# ArduinoInterface_v2_1.net
KiCad netlist of a schematic drawn in EAGLE
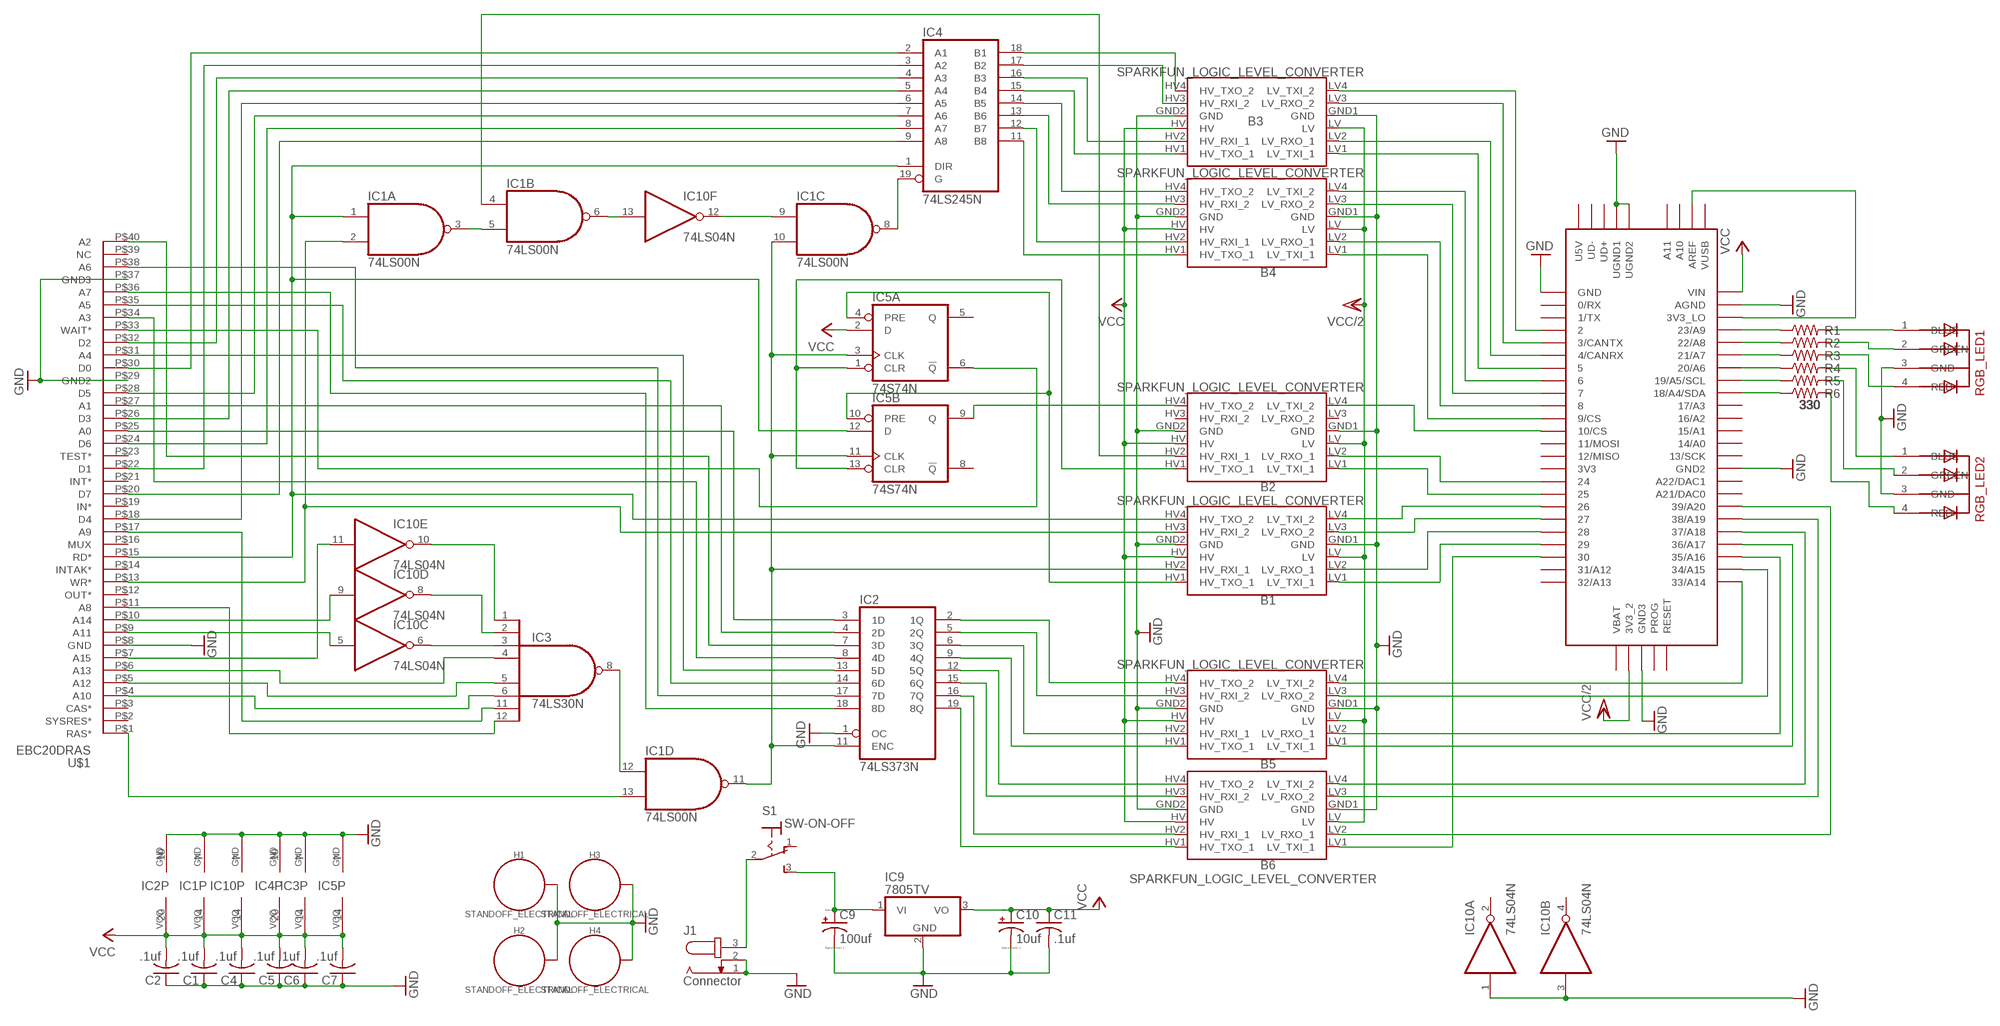
[diagram p0: schematic, sheet 1]

(export (version "E")
  (design (tool "Eeschema 10.0.6"))
  (components
    (comp (ref "B1")
      (value "SPARKFUN_LOGIC_LEVEL_CONVERTER")
      (footprint "eagle-import:SPARKFUN_LOGIC_LEVEL_CONVERTER")
      (libsource (lib "eagle-import") (part "SPARKFUN_LOGIC_LEVEL_CONVERTER"))
    )
    (comp (ref "B2")
      (value "SPARKFUN_LOGIC_LEVEL_CONVERTER")
      (footprint "eagle-import:SPARKFUN_LOGIC_LEVEL_CONVERTER")
      (libsource (lib "eagle-import") (part "SPARKFUN_LOGIC_LEVEL_CONVERTER"))
    )
    (comp (ref "B3")
      (value "SPARKFUN_LOGIC_LEVEL_CONVERTER")
      (footprint "eagle-import:SPARKFUN_LOGIC_LEVEL_CONVERTER")
      (libsource (lib "eagle-import") (part "SPARKFUN_LOGIC_LEVEL_CONVERTER"))
    )
    (comp (ref "B4")
      (value "SPARKFUN_LOGIC_LEVEL_CONVERTER")
      (footprint "eagle-import:SPARKFUN_LOGIC_LEVEL_CONVERTER")
      (libsource (lib "eagle-import") (part "SPARKFUN_LOGIC_LEVEL_CONVERTER"))
    )
    (comp (ref "B5")
      (value "SPARKFUN_LOGIC_LEVEL_CONVERTER")
      (footprint "eagle-import:SPARKFUN_LOGIC_LEVEL_CONVERTER")
      (libsource (lib "eagle-import") (part "SPARKFUN_LOGIC_LEVEL_CONVERTER"))
    )
    (comp (ref "B6")
      (value "SPARKFUN_LOGIC_LEVEL_CONVERTER")
      (footprint "eagle-import:SPARKFUN_LOGIC_LEVEL_CONVERTER")
      (libsource (lib "eagle-import") (part "SPARKFUN_LOGIC_LEVEL_CONVERTER"))
    )
    (comp (ref "C1")
      (value ".1uf")
      (footprint "eagle-import:C025-025X050")
      (libsource (lib "eagle-import") (part "C-US025-025X050"))
    )
    (comp (ref "C2")
      (value ".1uf")
      (footprint "eagle-import:C025-025X050")
      (libsource (lib "eagle-import") (part "C-US025-025X050"))
    )
    (comp (ref "C4")
      (value ".1uf")
      (footprint "eagle-import:C025-025X050")
      (libsource (lib "eagle-import") (part "C-US025-025X050"))
    )
    (comp (ref "C5")
      (value ".1uf")
      (footprint "eagle-import:C025-025X050")
      (libsource (lib "eagle-import") (part "C-US025-025X050"))
    )
    (comp (ref "C6")
      (value ".1uf")
      (footprint "eagle-import:C025-025X050")
      (libsource (lib "eagle-import") (part "C-US025-025X050"))
    )
    (comp (ref "C7")
      (value ".1uf")
      (footprint "eagle-import:C025-025X050")
      (libsource (lib "eagle-import") (part "C-US025-025X050"))
    )
    (comp (ref "C9")
      (value "100uf")
      (footprint "eagle-import:E5-6")
      (libsource (lib "eagle-import") (part "CPOL-USE5-6"))
    )
    (comp (ref "C10")
      (value "10uf")
      (footprint "eagle-import:E5-6")
      (libsource (lib "eagle-import") (part "CPOL-USE5-6"))
    )
    (comp (ref "C11")
      (value ".1uf")
      (footprint "eagle-import:C025-025X050")
      (libsource (lib "eagle-import") (part "C-US025-025X050"))
    )
    (comp (ref "H1")
      (value "STANDOFF_ELECTRICAL")
      (footprint "eagle-import:STANDOFF-ELECTRICAL")
      (libsource (lib "eagle-import") (part "STANDOFF_ELECTRICAL"))
    )
    (comp (ref "H2")
      (value "STANDOFF_ELECTRICAL")
      (footprint "eagle-import:STANDOFF-ELECTRICAL")
      (libsource (lib "eagle-import") (part "STANDOFF_ELECTRICAL"))
    )
    (comp (ref "H3")
      (value "STANDOFF_ELECTRICAL")
      (footprint "eagle-import:STANDOFF-ELECTRICAL")
      (libsource (lib "eagle-import") (part "STANDOFF_ELECTRICAL"))
    )
    (comp (ref "H4")
      (value "STANDOFF_ELECTRICAL")
      (footprint "eagle-import:STANDOFF-ELECTRICAL")
      (libsource (lib "eagle-import") (part "STANDOFF_ELECTRICAL"))
    )
    (comp (ref "IC1")
      (value "74LS00N")
      (footprint "eagle-import:DIL14")
      (libsource (lib "eagle-import") (part "7400NLS"))
    )
    (comp (ref "IC2")
      (value "74LS373N")
      (footprint "eagle-import:DIL20")
      (libsource (lib "eagle-import") (part "74373NLS"))
    )
    (comp (ref "IC3")
      (value "74LS30N")
      (footprint "eagle-import:DIL14")
      (libsource (lib "eagle-import") (part "7430NLS"))
    )
    (comp (ref "IC4")
      (value "74LS245N")
      (footprint "eagle-import:DIL20")
      (libsource (lib "eagle-import") (part "74245NLS"))
    )
    (comp (ref "IC5")
      (value "74S74N")
      (footprint "eagle-import:DIL14")
      (libsource (lib "eagle-import") (part "7474NS"))
    )
    (comp (ref "IC9")
      (value "7805TV")
      (footprint "eagle-import:TO220V")
      (libsource (lib "eagle-import") (part "78TV05"))
    )
    (comp (ref "IC10")
      (value "74LS04N")
      (footprint "eagle-import:DIL14")
      (libsource (lib "eagle-import") (part "7404NLS"))
    )
    (comp (ref "J1")
      (value "Connector")
      (footprint "eagle-import:SPC4077")
      (libsource (lib "eagle-import") (part "JACK-PLUG0"))
    )
    (comp (ref "R1")
      (value "330")
      (footprint "eagle-import:0204V")
      (libsource (lib "eagle-import") (part "R-US_0204/2V"))
    )
    (comp (ref "R2")
      (value "330")
      (footprint "eagle-import:0204V")
      (libsource (lib "eagle-import") (part "R-US_0204/2V"))
    )
    (comp (ref "R3")
      (value "330")
      (footprint "eagle-import:0204V")
      (libsource (lib "eagle-import") (part "R-US_0204/2V"))
    )
    (comp (ref "R4")
      (value "330")
      (footprint "eagle-import:0204V")
      (libsource (lib "eagle-import") (part "R-US_0204/2V"))
    )
    (comp (ref "R5")
      (value "330")
      (footprint "eagle-import:0204V")
      (libsource (lib "eagle-import") (part "R-US_0204/2V"))
    )
    (comp (ref "R6")
      (value "330")
      (footprint "eagle-import:0204V")
      (libsource (lib "eagle-import") (part "R-US_0204/2V"))
    )
    (comp (ref "RGB_LED1")
      (value "5MMRGBLED")
      (footprint "eagle-import:LED5MMRGB")
      (libsource (lib "eagle-import") (part "5MMRGBLED"))
    )
    (comp (ref "RGB_LED2")
      (value "5MMRGBLED")
      (footprint "eagle-import:LED5MMRGB")
      (libsource (lib "eagle-import") (part "5MMRGBLED"))
    )
    (comp (ref "S1")
      (value "SW-ON-OFF")
      (footprint "eagle-import:M9040P")
      (libsource (lib "eagle-import") (part "M9040P"))
    )
    (comp (ref "U$1")
      (value "EBC20DRAS")
      (footprint "eagle-import:EBC20DRAS")
      (libsource (lib "eagle-import") (part "EBC20DRAS"))
    )
    (comp (ref "U$2")
      (value "TEENSY_3.5/3.6")
      (footprint "eagle-import:TEENSY_3.5_3.6")
      (libsource (lib "eagle-import") (part "TEENSY_3.5/3.6"))
    )
  )
  (nets
    (net (code "1") (name "GND") (class "Default")
      (node (ref "B1") (pin "GND1") (pinfunction "GND_GND1") (pintype "power_in"))
      (node (ref "B1") (pin "GND2") (pinfunction "GND_GND2") (pintype "power_in"))
      (node (ref "B2") (pin "GND1") (pinfunction "GND_GND1") (pintype "power_in"))
      (node (ref "B2") (pin "GND2") (pinfunction "GND_GND2") (pintype "power_in"))
      (node (ref "B3") (pin "GND1") (pinfunction "GND_GND1") (pintype "power_in"))
      (node (ref "B3") (pin "GND2") (pinfunction "GND_GND2") (pintype "power_in"))
      (node (ref "B4") (pin "GND1") (pinfunction "GND_GND1") (pintype "power_in"))
      (node (ref "B4") (pin "GND2") (pinfunction "GND_GND2") (pintype "power_in"))
      (node (ref "B5") (pin "GND1") (pinfunction "GND_GND1") (pintype "power_in"))
      (node (ref "B5") (pin "GND2") (pinfunction "GND_GND2") (pintype "power_in"))
      (node (ref "B6") (pin "GND1") (pinfunction "GND_GND1") (pintype "power_in"))
      (node (ref "B6") (pin "GND2") (pinfunction "GND_GND2") (pintype "power_in"))
      (node (ref "C1") (pin "1") (pinfunction "1_1") (pintype "passive"))
      (node (ref "C10") (pin "-") (pinfunction "-_-") (pintype "passive"))
      (node (ref "C11") (pin "2") (pinfunction "2_2") (pintype "passive"))
      (node (ref "C2") (pin "1") (pinfunction "1_1") (pintype "passive"))
      (node (ref "C4") (pin "1") (pinfunction "1_1") (pintype "passive"))
      (node (ref "C5") (pin "1") (pinfunction "1_1") (pintype "passive"))
      (node (ref "C6") (pin "1") (pinfunction "1_1") (pintype "passive"))
      (node (ref "C7") (pin "1") (pinfunction "1_1") (pintype "passive"))
      (node (ref "C9") (pin "-") (pinfunction "-_-") (pintype "passive"))
      (node (ref "H1") (pin "P1") (pinfunction "P$1_P1") (pintype "bidirectional"))
      (node (ref "H2") (pin "P1") (pinfunction "P$1_P1") (pintype "bidirectional"))
      (node (ref "H3") (pin "P1") (pinfunction "P$1_P1") (pintype "bidirectional"))
      (node (ref "H4") (pin "P1") (pinfunction "P$1_P1") (pintype "bidirectional"))
      (node (ref "IC1") (pin "7") (pinfunction "GND_7") (pintype "power_in"))
      (node (ref "IC10") (pin "1") (pinfunction "I_1") (pintype "input"))
      (node (ref "IC10") (pin "3") (pinfunction "I_3") (pintype "input"))
      (node (ref "IC10") (pin "7") (pinfunction "GND_7") (pintype "power_in"))
      (node (ref "IC2") (pin "1") (pinfunction "OC_1") (pintype "input"))
      (node (ref "IC2") (pin "10") (pinfunction "GND_10") (pintype "power_in"))
      (node (ref "IC3") (pin "7") (pinfunction "GND_7") (pintype "power_in"))
      (node (ref "IC4") (pin "10") (pinfunction "GND_10") (pintype "power_in"))
      (node (ref "IC5") (pin "7") (pinfunction "GND_7") (pintype "power_in"))
      (node (ref "IC9") (pin "2") (pinfunction "GND_2") (pintype "passive"))
      (node (ref "J1") (pin "1") (pinfunction "1_1") (pintype "passive"))
      (node (ref "J1") (pin "2") (pinfunction "2_2") (pintype "passive"))
      (node (ref "RGB_LED1") (pin "3") (pinfunction "GND_3") (pintype "bidirectional"))
      (node (ref "RGB_LED2") (pin "3") (pinfunction "GND_3") (pintype "bidirectional"))
      (node (ref "U$1") (pin "P$29") (pinfunction "GND2_P$29") (pintype "bidirectional"))
      (node (ref "U$1") (pin "P$37") (pinfunction "GND3_P$37") (pintype "bidirectional"))
      (node (ref "U$1") (pin "P$8") (pinfunction "GND_P$8") (pintype "bidirectional"))
      (node (ref "U$2") (pin "AGND") (pinfunction "AGND_AGND") (pintype "bidirectional"))
      (node (ref "U$2") (pin "GND") (pinfunction "GND_GND") (pintype "bidirectional"))
      (node (ref "U$2") (pin "GND2") (pinfunction "GND2_GND2") (pintype "bidirectional"))
      (node (ref "U$2") (pin "GND3") (pinfunction "GND3_GND3") (pintype "bidirectional"))
      (node (ref "U$2") (pin "UGND1") (pinfunction "UGND1_UGND1") (pintype "bidirectional"))
      (node (ref "U$2") (pin "UGND2") (pinfunction "UGND2_UGND2") (pintype "bidirectional"))
    )
    (net (code "2") (name "Net-(B1-HV_RXI_1)") (class "Default")
      (node (ref "B1") (pin "HV2") (pinfunction "HV_RXI_1_HV2") (pintype "bidirectional"))
      (node (ref "IC1") (pin "10") (pinfunction "I1_10") (pintype "input"))
      (node (ref "IC1") (pin "11") (pinfunction "O_11") (pintype "output"))
      (node (ref "IC2") (pin "11") (pinfunction "ENC_11") (pintype "input"))
      (node (ref "IC5") (pin "11") (pinfunction "CLK_11") (pintype "input"))
      (node (ref "IC5") (pin "3") (pinfunction "CLK_3") (pintype "input"))
    )
    (net (code "3") (name "Net-(B1-HV_RXI_2)") (class "Default")
      (node (ref "B1") (pin "HV3") (pinfunction "HV_RXI_2_HV3") (pintype "bidirectional"))
      (node (ref "IC1") (pin "2") (pinfunction "I1_2") (pintype "input"))
      (node (ref "U$1") (pin "P$13") (pinfunction "WR*_P$13") (pintype "bidirectional"))
    )
    (net (code "4") (name "Net-(B1-HV_TXO_1)") (class "Default")
      (node (ref "B1") (pin "HV1") (pinfunction "HV_TXO_1_HV1") (pintype "bidirectional"))
      (node (ref "IC5") (pin "10") (pinfunction "PRE_10") (pintype "input"))
      (node (ref "IC5") (pin "4") (pinfunction "PRE_4") (pintype "input"))
    )
    (net (code "5") (name "Net-(B1-HV_TXO_2)") (class "Default")
      (node (ref "B1") (pin "HV4") (pinfunction "HV_TXO_2_HV4") (pintype "bidirectional"))
      (node (ref "IC1") (pin "1") (pinfunction "I0_1") (pintype "input"))
      (node (ref "IC4") (pin "1") (pinfunction "DIR_1") (pintype "input"))
      (node (ref "IC5") (pin "12") (pinfunction "D_12") (pintype "input"))
      (node (ref "U$1") (pin "P$15") (pinfunction "RD*_P$15") (pintype "bidirectional"))
    )
    (net (code "6") (name "Net-(B1-LV_RXO_1)") (class "Default")
      (node (ref "B1") (pin "LV2") (pinfunction "LV_RXO_1_LV2") (pintype "bidirectional"))
      (node (ref "U$2") (pin "28") (pinfunction "28_28") (pintype "bidirectional"))
    )
    (net (code "7") (name "Net-(B1-LV_RXO_2)") (class "Default")
      (node (ref "B1") (pin "LV3") (pinfunction "LV_RXO_2_LV3") (pintype "bidirectional"))
      (node (ref "U$2") (pin "27") (pinfunction "27_27") (pintype "bidirectional"))
    )
    (net (code "8") (name "Net-(B1-LV_TXI_1)") (class "Default")
      (node (ref "B1") (pin "LV1") (pinfunction "LV_TXI_1_LV1") (pintype "bidirectional"))
      (node (ref "U$2") (pin "29") (pinfunction "29_29") (pintype "bidirectional"))
    )
    (net (code "9") (name "Net-(B1-LV_TXI_2)") (class "Default")
      (node (ref "B1") (pin "LV4") (pinfunction "LV_TXI_2_LV4") (pintype "bidirectional"))
      (node (ref "U$2") (pin "26") (pinfunction "26_26") (pintype "bidirectional"))
    )
    (net (code "10") (name "Net-(B2-HV_RXI_1)") (class "Default")
      (node (ref "B2") (pin "HV2") (pinfunction "HV_RXI_1_HV2") (pintype "bidirectional"))
      (node (ref "IC1") (pin "4") (pinfunction "I0_4") (pintype "input"))
    )
    (net (code "11") (name "Net-(B2-HV_TXO_1)") (class "Default")
      (node (ref "B2") (pin "HV1") (pinfunction "HV_TXO_1_HV1") (pintype "bidirectional"))
      (node (ref "IC5") (pin "1") (pinfunction "CLR_1") (pintype "input"))
      (node (ref "IC5") (pin "13") (pinfunction "CLR_13") (pintype "input"))
    )
    (net (code "12") (name "Net-(B2-HV_TXO_2)") (class "Default")
      (node (ref "B2") (pin "HV4") (pinfunction "HV_TXO_2_HV4") (pintype "bidirectional"))
      (node (ref "IC5") (pin "9") (pinfunction "Q_9") (pintype "output"))
    )
    (net (code "13") (name "Net-(B2-LV_RXO_1)") (class "Default")
      (node (ref "B2") (pin "LV2") (pinfunction "LV_RXO_1_LV2") (pintype "bidirectional"))
      (node (ref "U$2") (pin "24") (pinfunction "24_24") (pintype "bidirectional"))
    )
    (net (code "14") (name "Net-(B2-LV_TXI_1)") (class "Default")
      (node (ref "B2") (pin "LV1") (pinfunction "LV_TXI_1_LV1") (pintype "bidirectional"))
      (node (ref "U$2") (pin "25") (pinfunction "25_25") (pintype "bidirectional"))
    )
    (net (code "15") (name "Net-(B2-LV_TXI_2)") (class "Default")
      (node (ref "B2") (pin "LV4") (pinfunction "LV_TXI_2_LV4") (pintype "bidirectional"))
      (node (ref "U$2") (pin "10/CS") (pinfunction "10/CS_10/CS") (pintype "bidirectional"))
    )
    (net (code "16") (name "Net-(B3-HV_RXI_1)") (class "Default")
      (node (ref "B3") (pin "HV2") (pinfunction "HV_RXI_1_HV2") (pintype "bidirectional"))
      (node (ref "IC4") (pin "16") (pinfunction "B3_16") (pintype "bidirectional"))
    )
    (net (code "17") (name "Net-(B3-HV_RXI_2)") (class "Default")
      (node (ref "B3") (pin "HV3") (pinfunction "HV_RXI_2_HV3") (pintype "bidirectional"))
      (node (ref "IC4") (pin "17") (pinfunction "B2_17") (pintype "bidirectional"))
    )
    (net (code "18") (name "Net-(B3-HV_TXO_1)") (class "Default")
      (node (ref "B3") (pin "HV1") (pinfunction "HV_TXO_1_HV1") (pintype "bidirectional"))
      (node (ref "IC4") (pin "15") (pinfunction "B4_15") (pintype "bidirectional"))
    )
    (net (code "19") (name "Net-(B3-HV_TXO_2)") (class "Default")
      (node (ref "B3") (pin "HV4") (pinfunction "HV_TXO_2_HV4") (pintype "bidirectional"))
      (node (ref "IC4") (pin "18") (pinfunction "B1_18") (pintype "bidirectional"))
    )
    (net (code "20") (name "Net-(B3-LV_RXO_1)") (class "Default")
      (node (ref "B3") (pin "LV2") (pinfunction "LV_RXO_1_LV2") (pintype "bidirectional"))
      (node (ref "U$2") (pin "4/CANRX") (pinfunction "4/CANRX_4/CANRX") (pintype "bidirectional"))
    )
    (net (code "21") (name "Net-(B3-LV_RXO_2)") (class "Default")
      (node (ref "B3") (pin "LV3") (pinfunction "LV_RXO_2_LV3") (pintype "bidirectional"))
      (node (ref "U$2") (pin "3/CANTX") (pinfunction "3/CANTX_3/CANTX") (pintype "bidirectional"))
    )
    (net (code "22") (name "Net-(B3-LV_TXI_1)") (class "Default")
      (node (ref "B3") (pin "LV1") (pinfunction "LV_TXI_1_LV1") (pintype "bidirectional"))
      (node (ref "U$2") (pin "5") (pinfunction "5_5") (pintype "bidirectional"))
    )
    (net (code "23") (name "Net-(B3-LV_TXI_2)") (class "Default")
      (node (ref "B3") (pin "LV4") (pinfunction "LV_TXI_2_LV4") (pintype "bidirectional"))
      (node (ref "U$2") (pin "2") (pinfunction "2_2") (pintype "bidirectional"))
    )
    (net (code "24") (name "Net-(B4-HV_RXI_1)") (class "Default")
      (node (ref "B4") (pin "HV2") (pinfunction "HV_RXI_1_HV2") (pintype "bidirectional"))
      (node (ref "IC4") (pin "12") (pinfunction "B7_12") (pintype "bidirectional"))
    )
    (net (code "25") (name "Net-(B4-HV_RXI_2)") (class "Default")
      (node (ref "B4") (pin "HV3") (pinfunction "HV_RXI_2_HV3") (pintype "bidirectional"))
      (node (ref "IC4") (pin "13") (pinfunction "B6_13") (pintype "bidirectional"))
    )
    (net (code "26") (name "Net-(B4-HV_TXO_1)") (class "Default")
      (node (ref "B4") (pin "HV1") (pinfunction "HV_TXO_1_HV1") (pintype "bidirectional"))
      (node (ref "IC4") (pin "11") (pinfunction "B8_11") (pintype "bidirectional"))
    )
    (net (code "27") (name "Net-(B4-HV_TXO_2)") (class "Default")
      (node (ref "B4") (pin "HV4") (pinfunction "HV_TXO_2_HV4") (pintype "bidirectional"))
      (node (ref "IC4") (pin "14") (pinfunction "B5_14") (pintype "bidirectional"))
    )
    (net (code "28") (name "Net-(B4-LV_RXO_1)") (class "Default")
      (node (ref "B4") (pin "LV2") (pinfunction "LV_RXO_1_LV2") (pintype "bidirectional"))
      (node (ref "U$2") (pin "8") (pinfunction "8_8") (pintype "bidirectional"))
    )
    (net (code "29") (name "Net-(B4-LV_RXO_2)") (class "Default")
      (node (ref "B4") (pin "LV3") (pinfunction "LV_RXO_2_LV3") (pintype "bidirectional"))
      (node (ref "U$2") (pin "7") (pinfunction "7_7") (pintype "bidirectional"))
    )
    (net (code "30") (name "Net-(B4-LV_TXI_1)") (class "Default")
      (node (ref "B4") (pin "LV1") (pinfunction "LV_TXI_1_LV1") (pintype "bidirectional"))
      (node (ref "U$2") (pin "9/CS") (pinfunction "9/CS_9/CS") (pintype "bidirectional"))
    )
    (net (code "31") (name "Net-(B4-LV_TXI_2)") (class "Default")
      (node (ref "B4") (pin "LV4") (pinfunction "LV_TXI_2_LV4") (pintype "bidirectional"))
      (node (ref "U$2") (pin "6") (pinfunction "6_6") (pintype "bidirectional"))
    )
    (net (code "32") (name "Net-(B5-HV_RXI_1)") (class "Default")
      (node (ref "B5") (pin "HV2") (pinfunction "HV_RXI_1_HV2") (pintype "bidirectional"))
      (node (ref "IC2") (pin "6") (pinfunction "3Q_6") (pintype "tri_state"))
    )
    (net (code "33") (name "Net-(B5-HV_RXI_2)") (class "Default")
      (node (ref "B5") (pin "HV3") (pinfunction "HV_RXI_2_HV3") (pintype "bidirectional"))
      (node (ref "IC2") (pin "5") (pinfunction "2Q_5") (pintype "tri_state"))
    )
    (net (code "34") (name "Net-(B5-HV_TXO_1)") (class "Default")
      (node (ref "B5") (pin "HV1") (pinfunction "HV_TXO_1_HV1") (pintype "bidirectional"))
      (node (ref "IC2") (pin "9") (pinfunction "4Q_9") (pintype "tri_state"))
    )
    (net (code "35") (name "Net-(B5-HV_TXO_2)") (class "Default")
      (node (ref "B5") (pin "HV4") (pinfunction "HV_TXO_2_HV4") (pintype "bidirectional"))
      (node (ref "IC2") (pin "2") (pinfunction "1Q_2") (pintype "tri_state"))
    )
    (net (code "36") (name "Net-(B5-LV_RXO_1)") (class "Default")
      (node (ref "B5") (pin "LV2") (pinfunction "LV_RXO_1_LV2") (pintype "bidirectional"))
      (node (ref "U$2") (pin "35/A16") (pinfunction "35/A16_35/A16") (pintype "bidirectional"))
    )
    (net (code "37") (name "Net-(B5-LV_RXO_2)") (class "Default")
      (node (ref "B5") (pin "LV3") (pinfunction "LV_RXO_2_LV3") (pintype "bidirectional"))
      (node (ref "U$2") (pin "34/A15") (pinfunction "34/A15_34/A15") (pintype "bidirectional"))
    )
    (net (code "38") (name "Net-(B5-LV_TXI_1)") (class "Default")
      (node (ref "B5") (pin "LV1") (pinfunction "LV_TXI_1_LV1") (pintype "bidirectional"))
      (node (ref "U$2") (pin "36/A17") (pinfunction "36/A17_36/A17") (pintype "bidirectional"))
    )
    (net (code "39") (name "Net-(B5-LV_TXI_2)") (class "Default")
      (node (ref "B5") (pin "LV4") (pinfunction "LV_TXI_2_LV4") (pintype "bidirectional"))
      (node (ref "U$2") (pin "33/A14") (pinfunction "33/A14_33/A14") (pintype "bidirectional"))
    )
    (net (code "40") (name "Net-(B6-HV_RXI_1)") (class "Default")
      (node (ref "B6") (pin "HV2") (pinfunction "HV_RXI_1_HV2") (pintype "bidirectional"))
      (node (ref "IC2") (pin "16") (pinfunction "7Q_16") (pintype "tri_state"))
    )
    (net (code "41") (name "Net-(B6-HV_RXI_2)") (class "Default")
      (node (ref "B6") (pin "HV3") (pinfunction "HV_RXI_2_HV3") (pintype "bidirectional"))
      (node (ref "IC2") (pin "15") (pinfunction "6Q_15") (pintype "tri_state"))
    )
    (net (code "42") (name "Net-(B6-HV_TXO_1)") (class "Default")
      (node (ref "B6") (pin "HV1") (pinfunction "HV_TXO_1_HV1") (pintype "bidirectional"))
      (node (ref "IC2") (pin "19") (pinfunction "8Q_19") (pintype "tri_state"))
    )
    (net (code "43") (name "Net-(B6-HV_TXO_2)") (class "Default")
      (node (ref "B6") (pin "HV4") (pinfunction "HV_TXO_2_HV4") (pintype "bidirectional"))
      (node (ref "IC2") (pin "12") (pinfunction "5Q_12") (pintype "tri_state"))
    )
    (net (code "44") (name "Net-(B6-LV_RXO_1)") (class "Default")
      (node (ref "B6") (pin "LV2") (pinfunction "LV_RXO_1_LV2") (pintype "bidirectional"))
      (node (ref "U$2") (pin "39/A20") (pinfunction "39/A20_39/A20") (pintype "bidirectional"))
    )
    (net (code "45") (name "Net-(B6-LV_RXO_2)") (class "Default")
      (node (ref "B6") (pin "LV3") (pinfunction "LV_RXO_2_LV3") (pintype "bidirectional"))
      (node (ref "U$2") (pin "38/A19") (pinfunction "38/A19_38/A19") (pintype "bidirectional"))
    )
    (net (code "46") (name "Net-(B6-LV_TXI_1)") (class "Default")
      (node (ref "B6") (pin "LV1") (pinfunction "LV_TXI_1_LV1") (pintype "bidirectional"))
      (node (ref "U$2") (pin "30") (pinfunction "30_30") (pintype "bidirectional"))
    )
    (net (code "47") (name "Net-(B6-LV_TXI_2)") (class "Default")
      (node (ref "B6") (pin "LV4") (pinfunction "LV_TXI_2_LV4") (pintype "bidirectional"))
      (node (ref "U$2") (pin "37/A18") (pinfunction "37/A18_37/A18") (pintype "bidirectional"))
    )
    (net (code "48") (name "Net-(IC1A-O)") (class "Default")
      (node (ref "IC1") (pin "3") (pinfunction "O_3") (pintype "output"))
      (node (ref "IC1") (pin "5") (pinfunction "I1_5") (pintype "input"))
    )
    (net (code "49") (name "Net-(IC1C-O)") (class "Default")
      (node (ref "IC1") (pin "8") (pinfunction "O_8") (pintype "output"))
      (node (ref "IC4") (pin "19") (pinfunction "G_19") (pintype "input"))
    )
    (net (code "50") (name "Net-(IC1D-I0)") (class "Default")
      (node (ref "IC1") (pin "12") (pinfunction "I0_12") (pintype "input"))
      (node (ref "IC3") (pin "8") (pinfunction "O_8") (pintype "output"))
    )
    (net (code "51") (name "Net-(IC1D-I1)") (class "Default")
      (node (ref "IC1") (pin "13") (pinfunction "I1_13") (pintype "input"))
      (node (ref "U$1") (pin "P$1") (pinfunction "RAS*_P$1") (pintype "bidirectional"))
    )
    (net (code "52") (name "Net-(IC2A-1D)") (class "Default")
      (node (ref "IC2") (pin "3") (pinfunction "1D_3") (pintype "input"))
      (node (ref "U$1") (pin "P$25") (pinfunction "A0_P$25") (pintype "bidirectional"))
    )
    (net (code "53") (name "Net-(IC2A-2D)") (class "Default")
      (node (ref "IC2") (pin "4") (pinfunction "2D_4") (pintype "input"))
      (node (ref "U$1") (pin "P$27") (pinfunction "A1_P$27") (pintype "bidirectional"))
    )
    (net (code "54") (name "Net-(IC2A-3D)") (class "Default")
      (node (ref "IC2") (pin "7") (pinfunction "3D_7") (pintype "input"))
      (node (ref "U$1") (pin "P$40") (pinfunction "A2_P$40") (pintype "bidirectional"))
    )
    (net (code "55") (name "Net-(IC2A-4D)") (class "Default")
      (node (ref "IC2") (pin "8") (pinfunction "4D_8") (pintype "input"))
      (node (ref "U$1") (pin "P$34") (pinfunction "A3_P$34") (pintype "bidirectional"))
    )
    (net (code "56") (name "Net-(IC2A-5D)") (class "Default")
      (node (ref "IC2") (pin "13") (pinfunction "5D_13") (pintype "input"))
      (node (ref "U$1") (pin "P$31") (pinfunction "A4_P$31") (pintype "bidirectional"))
    )
    (net (code "57") (name "Net-(IC2A-6D)") (class "Default")
      (node (ref "IC2") (pin "14") (pinfunction "6D_14") (pintype "input"))
      (node (ref "U$1") (pin "P$35") (pinfunction "A5_P$35") (pintype "bidirectional"))
    )
    (net (code "58") (name "Net-(IC2A-7D)") (class "Default")
      (node (ref "IC2") (pin "17") (pinfunction "7D_17") (pintype "input"))
      (node (ref "U$1") (pin "P$38") (pinfunction "A6_P$38") (pintype "bidirectional"))
    )
    (net (code "59") (name "Net-(IC2A-8D)") (class "Default")
      (node (ref "IC2") (pin "18") (pinfunction "8D_18") (pintype "input"))
      (node (ref "U$1") (pin "P$36") (pinfunction "A7_P$36") (pintype "bidirectional"))
    )
    (net (code "60") (name "Net-(IC3A-I3)") (class "Default")
      (node (ref "IC3") (pin "4") (pinfunction "I3_4") (pintype "input"))
      (node (ref "U$1") (pin "P$6") (pinfunction "A13_P$6") (pintype "bidirectional"))
    )
    (net (code "61") (name "Net-(IC3A-I4)") (class "Default")
      (node (ref "IC3") (pin "5") (pinfunction "I4_5") (pintype "input"))
      (node (ref "U$1") (pin "P$5") (pinfunction "A12_P$5") (pintype "bidirectional"))
    )
    (net (code "62") (name "Net-(IC3A-I5)") (class "Default")
      (node (ref "IC3") (pin "6") (pinfunction "I5_6") (pintype "input"))
      (node (ref "U$1") (pin "P$4") (pinfunction "A10_P$4") (pintype "bidirectional"))
    )
    (net (code "63") (name "Net-(IC3A-I6)") (class "Default")
      (node (ref "IC3") (pin "11") (pinfunction "I6_11") (pintype "input"))
      (node (ref "U$1") (pin "P$17") (pinfunction "A9_P$17") (pintype "bidirectional"))
    )
    (net (code "64") (name "Net-(IC3A-I7)") (class "Default")
      (node (ref "IC3") (pin "12") (pinfunction "I7_12") (pintype "input"))
      (node (ref "U$1") (pin "P$11") (pinfunction "A8_P$11") (pintype "bidirectional"))
    )
    (net (code "65") (name "Net-(IC4A-A1)") (class "Default")
      (node (ref "IC4") (pin "2") (pinfunction "A1_2") (pintype "bidirectional"))
      (node (ref "U$1") (pin "P$30") (pinfunction "D0_P$30") (pintype "bidirectional"))
    )
    (net (code "66") (name "Net-(IC4A-A2)") (class "Default")
      (node (ref "IC4") (pin "3") (pinfunction "A2_3") (pintype "bidirectional"))
      (node (ref "U$1") (pin "P$22") (pinfunction "D1_P$22") (pintype "bidirectional"))
    )
    (net (code "67") (name "Net-(IC4A-A3)") (class "Default")
      (node (ref "IC4") (pin "4") (pinfunction "A3_4") (pintype "bidirectional"))
      (node (ref "U$1") (pin "P$32") (pinfunction "D2_P$32") (pintype "bidirectional"))
    )
    (net (code "68") (name "Net-(IC4A-A4)") (class "Default")
      (node (ref "IC4") (pin "5") (pinfunction "A4_5") (pintype "bidirectional"))
      (node (ref "U$1") (pin "P$26") (pinfunction "D3_P$26") (pintype "bidirectional"))
    )
    (net (code "69") (name "Net-(IC4A-A5)") (class "Default")
      (node (ref "IC4") (pin "6") (pinfunction "A5_6") (pintype "bidirectional"))
      (node (ref "U$1") (pin "P$18") (pinfunction "D4_P$18") (pintype "bidirectional"))
    )
    (net (code "70") (name "Net-(IC4A-A6)") (class "Default")
      (node (ref "IC4") (pin "7") (pinfunction "A6_7") (pintype "bidirectional"))
      (node (ref "U$1") (pin "P$28") (pinfunction "D5_P$28") (pintype "bidirectional"))
    )
    (net (code "71") (name "Net-(IC4A-A7)") (class "Default")
      (node (ref "IC4") (pin "8") (pinfunction "A7_8") (pintype "bidirectional"))
      (node (ref "U$1") (pin "P$24") (pinfunction "D6_P$24") (pintype "bidirectional"))
    )
    (net (code "72") (name "Net-(IC4A-A8)") (class "Default")
      (node (ref "IC4") (pin "9") (pinfunction "A8_9") (pintype "bidirectional"))
      (node (ref "U$1") (pin "P$20") (pinfunction "D7_P$20") (pintype "bidirectional"))
    )
    (net (code "73") (name "Net-(IC5A-~{Q})") (class "Default")
      (node (ref "IC5") (pin "6") (pinfunction "~{Q}_6") (pintype "output"))
      (node (ref "U$1") (pin "P$33") (pinfunction "WAIT*_P$33") (pintype "bidirectional"))
    )
    (net (code "74") (name "Net-(IC9-VI)") (class "Default")
      (node (ref "C9") (pin "+") (pinfunction "+_+") (pintype "passive"))
      (node (ref "IC9") (pin "1") (pinfunction "VI_1") (pintype "input"))
      (node (ref "S1") (pin "3") (pinfunction "S_3") (pintype "passive"))
    )
    (net (code "75") (name "Net-(IC10C-I)") (class "Default")
      (node (ref "IC10") (pin "5") (pinfunction "I_5") (pintype "input"))
      (node (ref "U$1") (pin "P$9") (pinfunction "A11_P$9") (pintype "bidirectional"))
    )
    (net (code "76") (name "Net-(IC10C-O)") (class "Default")
      (node (ref "IC10") (pin "6") (pinfunction "O_6") (pintype "output"))
      (node (ref "IC3") (pin "3") (pinfunction "I2_3") (pintype "input"))
    )
    (net (code "77") (name "Net-(IC10D-I)") (class "Default")
      (node (ref "IC10") (pin "9") (pinfunction "I_9") (pintype "input"))
      (node (ref "U$1") (pin "P$10") (pinfunction "A14_P$10") (pintype "bidirectional"))
    )
    (net (code "78") (name "Net-(IC10D-O)") (class "Default")
      (node (ref "IC10") (pin "8") (pinfunction "O_8") (pintype "output"))
      (node (ref "IC3") (pin "2") (pinfunction "I1_2") (pintype "input"))
    )
    (net (code "79") (name "Net-(IC10E-I)") (class "Default")
      (node (ref "IC10") (pin "11") (pinfunction "I_11") (pintype "input"))
      (node (ref "U$1") (pin "P$7") (pinfunction "A15_P$7") (pintype "bidirectional"))
    )
    (net (code "80") (name "Net-(IC10E-O)") (class "Default")
      (node (ref "IC10") (pin "10") (pinfunction "O_10") (pintype "output"))
      (node (ref "IC3") (pin "1") (pinfunction "I0_1") (pintype "input"))
    )
    (net (code "81") (name "Net-(IC10F-I)") (class "Default")
      (node (ref "IC1") (pin "6") (pinfunction "O_6") (pintype "output"))
      (node (ref "IC10") (pin "13") (pinfunction "I_13") (pintype "input"))
    )
    (net (code "82") (name "Net-(IC10F-O)") (class "Default")
      (node (ref "IC1") (pin "9") (pinfunction "I0_9") (pintype "input"))
      (node (ref "IC10") (pin "12") (pinfunction "O_12") (pintype "output"))
    )
    (net (code "83") (name "Net-(R1-Pad1)") (class "Default")
      (node (ref "R1") (pin "1") (pinfunction "1_1") (pintype "passive"))
      (node (ref "U$2") (pin "23/A9") (pinfunction "23/A9_23/A9") (pintype "bidirectional"))
    )
    (net (code "84") (name "Net-(R2-Pad1)") (class "Default")
      (node (ref "R2") (pin "1") (pinfunction "1_1") (pintype "passive"))
      (node (ref "U$2") (pin "22/A8") (pinfunction "22/A8_22/A8") (pintype "bidirectional"))
    )
    (net (code "85") (name "Net-(R3-Pad1)") (class "Default")
      (node (ref "R3") (pin "1") (pinfunction "1_1") (pintype "passive"))
      (node (ref "U$2") (pin "21/A7") (pinfunction "21/A7_21/A7") (pintype "bidirectional"))
    )
    (net (code "86") (name "Net-(R4-Pad1)") (class "Default")
      (node (ref "R4") (pin "1") (pinfunction "1_1") (pintype "passive"))
      (node (ref "U$2") (pin "20/A6") (pinfunction "20/A6_20/A6") (pintype "bidirectional"))
    )
    (net (code "87") (name "Net-(R5-Pad1)") (class "Default")
      (node (ref "R5") (pin "1") (pinfunction "1_1") (pintype "passive"))
      (node (ref "U$2") (pin "19/A5/SCL") (pinfunction "19/A5/SCL_19/A5/SCL") (pintype "bidirectional"))
    )
    (net (code "88") (name "Net-(R6-Pad1)") (class "Default")
      (node (ref "R6") (pin "1") (pinfunction "1_1") (pintype "passive"))
      (node (ref "U$2") (pin "18/A4/SDA") (pinfunction "18/A4/SDA_18/A4/SDA") (pintype "bidirectional"))
    )
    (net (code "89") (name "Net-(RGB_LED1-BLUE)") (class "Default")
      (node (ref "R1") (pin "2") (pinfunction "2_2") (pintype "passive"))
      (node (ref "RGB_LED1") (pin "1") (pinfunction "BLUE_1") (pintype "bidirectional"))
    )
    (net (code "90") (name "Net-(RGB_LED1-GREEN)") (class "Default")
      (node (ref "R2") (pin "2") (pinfunction "2_2") (pintype "passive"))
      (node (ref "RGB_LED1") (pin "2") (pinfunction "GREEN_2") (pintype "bidirectional"))
    )
    (net (code "91") (name "Net-(RGB_LED1-RED)") (class "Default")
      (node (ref "R3") (pin "2") (pinfunction "2_2") (pintype "passive"))
      (node (ref "RGB_LED1") (pin "4") (pinfunction "RED_4") (pintype "bidirectional"))
    )
    (net (code "92") (name "Net-(RGB_LED2-BLUE)") (class "Default")
      (node (ref "R4") (pin "2") (pinfunction "2_2") (pintype "passive"))
      (node (ref "RGB_LED2") (pin "1") (pinfunction "BLUE_1") (pintype "bidirectional"))
    )
    (net (code "93") (name "Net-(RGB_LED2-GREEN)") (class "Default")
      (node (ref "R5") (pin "2") (pinfunction "2_2") (pintype "passive"))
      (node (ref "RGB_LED2") (pin "2") (pinfunction "GREEN_2") (pintype "bidirectional"))
    )
    (net (code "94") (name "Net-(RGB_LED2-RED)") (class "Default")
      (node (ref "R6") (pin "2") (pinfunction "2_2") (pintype "passive"))
      (node (ref "RGB_LED2") (pin "4") (pinfunction "RED_4") (pintype "bidirectional"))
    )
    (net (code "95") (name "Net-(S1-P)") (class "Default")
      (node (ref "J1") (pin "3") (pinfunction "3_3") (pintype "passive"))
      (node (ref "S1") (pin "2") (pinfunction "P_2") (pintype "passive"))
    )
    (net (code "96") (name "Net-(U$2-Pad3V3_LO)") (class "Default")
      (node (ref "U$2") (pin "3V3_LO") (pinfunction "3V3_LO_3V3_LO") (pintype "bidirectional"))
      (node (ref "U$2") (pin "AREF") (pinfunction "AREF_AREF") (pintype "bidirectional"))
    )
    (net (code "97") (name "VCC") (class "Default")
      (node (ref "B1") (pin "HV") (pinfunction "HV_HV") (pintype "power_in"))
      (node (ref "B2") (pin "HV") (pinfunction "HV_HV") (pintype "power_in"))
      (node (ref "B3") (pin "HV") (pinfunction "HV_HV") (pintype "power_in"))
      (node (ref "B4") (pin "HV") (pinfunction "HV_HV") (pintype "power_in"))
      (node (ref "B5") (pin "HV") (pinfunction "HV_HV") (pintype "power_in"))
      (node (ref "B6") (pin "HV") (pinfunction "HV_HV") (pintype "power_in"))
      (node (ref "C1") (pin "2") (pinfunction "2_2") (pintype "passive"))
      (node (ref "C10") (pin "+") (pinfunction "+_+") (pintype "passive"))
      (node (ref "C11") (pin "1") (pinfunction "1_1") (pintype "passive"))
      (node (ref "C2") (pin "2") (pinfunction "2_2") (pintype "passive"))
      (node (ref "C4") (pin "2") (pinfunction "2_2") (pintype "passive"))
      (node (ref "C5") (pin "2") (pinfunction "2_2") (pintype "passive"))
      (node (ref "C6") (pin "2") (pinfunction "2_2") (pintype "passive"))
      (node (ref "C7") (pin "2") (pinfunction "2_2") (pintype "passive"))
      (node (ref "IC1") (pin "14") (pinfunction "VCC_14") (pintype "power_in"))
      (node (ref "IC10") (pin "14") (pinfunction "VCC_14") (pintype "power_in"))
      (node (ref "IC2") (pin "20") (pinfunction "VCC_20") (pintype "power_in"))
      (node (ref "IC3") (pin "14") (pinfunction "VCC_14") (pintype "power_in"))
      (node (ref "IC4") (pin "20") (pinfunction "VCC_20") (pintype "power_in"))
      (node (ref "IC5") (pin "14") (pinfunction "VCC_14") (pintype "power_in"))
      (node (ref "IC5") (pin "2") (pinfunction "D_2") (pintype "input"))
      (node (ref "IC9") (pin "3") (pinfunction "VO_3") (pintype "passive"))
      (node (ref "U$2") (pin "VIN") (pinfunction "VIN_VIN") (pintype "bidirectional"))
    )
    (net (code "98") (name "VCC{slash}2") (class "Default")
      (node (ref "B1") (pin "LV") (pinfunction "LV_LV") (pintype "power_in"))
      (node (ref "B2") (pin "LV") (pinfunction "LV_LV") (pintype "power_in"))
      (node (ref "B3") (pin "LV") (pinfunction "LV_LV") (pintype "power_in"))
      (node (ref "B4") (pin "LV") (pinfunction "LV_LV") (pintype "power_in"))
      (node (ref "B5") (pin "LV") (pinfunction "LV_LV") (pintype "power_in"))
      (node (ref "B6") (pin "LV") (pinfunction "LV_LV") (pintype "power_in"))
      (node (ref "U$2") (pin "3V3_2") (pinfunction "3V3_2_3V3_2") (pintype "bidirectional"))
    )
    (net (code "99") (name "unconnected-(B2-HV_RXI_2-PadHV3)") (class "Default")
      (node (ref "B2") (pin "HV3") (pinfunction "HV_RXI_2_HV3") (pintype "bidirectional"))
    )
    (net (code "100") (name "unconnected-(B2-LV_RXO_2-PadLV3)") (class "Default")
      (node (ref "B2") (pin "LV3") (pinfunction "LV_RXO_2_LV3") (pintype "bidirectional"))
    )
    (net (code "101") (name "unconnected-(IC5A-Q-Pad5)") (class "Default")
      (node (ref "IC5") (pin "5") (pinfunction "Q_5") (pintype "output"))
    )
    (net (code "102") (name "unconnected-(IC5B-~{Q}-Pad8)") (class "Default")
      (node (ref "IC5") (pin "8") (pinfunction "~{Q}_8") (pintype "output"))
    )
    (net (code "103") (name "unconnected-(IC10A-O-Pad2)") (class "Default")
      (node (ref "IC10") (pin "2") (pinfunction "O_2") (pintype "output"))
    )
    (net (code "104") (name "unconnected-(IC10B-O-Pad4)") (class "Default")
      (node (ref "IC10") (pin "4") (pinfunction "O_4") (pintype "output"))
    )
    (net (code "105") (name "unconnected-(S1-O-Pad1)") (class "Default")
      (node (ref "S1") (pin "1") (pinfunction "O_1") (pintype "passive"))
    )
    (net (code "106") (name "unconnected-(U$1-CAS*-PadP$3)") (class "Default")
      (node (ref "U$1") (pin "P$3") (pinfunction "CAS*_P$3") (pintype "bidirectional"))
    )
    (net (code "107") (name "unconnected-(U$1-IN*-PadP$19)") (class "Default")
      (node (ref "U$1") (pin "P$19") (pinfunction "IN*_P$19") (pintype "bidirectional"))
    )
    (net (code "108") (name "unconnected-(U$1-INT*-PadP$21)") (class "Default")
      (node (ref "U$1") (pin "P$21") (pinfunction "INT*_P$21") (pintype "bidirectional"))
    )
    (net (code "109") (name "unconnected-(U$1-INTAK*-PadP$14)") (class "Default")
      (node (ref "U$1") (pin "P$14") (pinfunction "INTAK*_P$14") (pintype "bidirectional"))
    )
    (net (code "110") (name "unconnected-(U$1-MUX-PadP$16)") (class "Default")
      (node (ref "U$1") (pin "P$16") (pinfunction "MUX_P$16") (pintype "bidirectional"))
    )
    (net (code "111") (name "unconnected-(U$1-NC-PadP$39)") (class "Default")
      (node (ref "U$1") (pin "P$39") (pinfunction "NC_P$39") (pintype "bidirectional"))
    )
    (net (code "112") (name "unconnected-(U$1-OUT*-PadP$12)") (class "Default")
      (node (ref "U$1") (pin "P$12") (pinfunction "OUT*_P$12") (pintype "bidirectional"))
    )
    (net (code "113") (name "unconnected-(U$1-SYSRES*-PadP$2)") (class "Default")
      (node (ref "U$1") (pin "P$2") (pinfunction "SYSRES*_P$2") (pintype "bidirectional"))
    )
    (net (code "114") (name "unconnected-(U$1-TEST*-PadP$23)") (class "Default")
      (node (ref "U$1") (pin "P$23") (pinfunction "TEST*_P$23") (pintype "bidirectional"))
    )
    (net (code "115") (name "unconnected-(U$2-A21{slash}DAC0-Pad21{slash}DAC0)") (class "Default")
      (node (ref "U$2") (pin "21/DAC0") (pinfunction "A21/DAC0_21/DAC0") (pintype "bidirectional"))
    )
    (net (code "116") (name "unconnected-(U$2-Pad0{slash}RX)") (class "Default")
      (node (ref "U$2") (pin "0/RX") (pinfunction "0/RX_0/RX") (pintype "bidirectional"))
    )
    (net (code "117") (name "unconnected-(U$2-Pad1{slash}TX)") (class "Default")
      (node (ref "U$2") (pin "1/TX") (pinfunction "1/TX_1/TX") (pintype "bidirectional"))
    )
    (net (code "118") (name "unconnected-(U$2-Pad3V3)") (class "Default")
      (node (ref "U$2") (pin "3V3") (pinfunction "3V3_3V3") (pintype "bidirectional"))
    )
    (net (code "119") (name "unconnected-(U$2-Pad11{slash}MOSI)") (class "Default")
      (node (ref "U$2") (pin "11/MOSI") (pinfunction "11/MOSI_11/MOSI") (pintype "bidirectional"))
    )
    (net (code "120") (name "unconnected-(U$2-Pad12{slash}MISO)") (class "Default")
      (node (ref "U$2") (pin "12/MISO") (pinfunction "12/MISO_12/MISO") (pintype "bidirectional"))
    )
    (net (code "121") (name "unconnected-(U$2-Pad13{slash}SCK)") (class "Default")
      (node (ref "U$2") (pin "13/SCK") (pinfunction "13/SCK_13/SCK") (pintype "bidirectional"))
    )
    (net (code "122") (name "unconnected-(U$2-Pad14{slash}A0)") (class "Default")
      (node (ref "U$2") (pin "14/A0") (pinfunction "14/A0_14/A0") (pintype "bidirectional"))
    )
    (net (code "123") (name "unconnected-(U$2-Pad15{slash}A1)") (class "Default")
      (node (ref "U$2") (pin "15/A1") (pinfunction "15/A1_15/A1") (pintype "bidirectional"))
    )
    (net (code "124") (name "unconnected-(U$2-Pad16{slash}A2)") (class "Default")
      (node (ref "U$2") (pin "16/A2") (pinfunction "16/A2_16/A2") (pintype "bidirectional"))
    )
    (net (code "125") (name "unconnected-(U$2-Pad17{slash}A3)") (class "Default")
      (node (ref "U$2") (pin "17/A3") (pinfunction "17/A3_17/A3") (pintype "bidirectional"))
    )
    (net (code "126") (name "unconnected-(U$2-Pad31{slash}A12)") (class "Default")
      (node (ref "U$2") (pin "31/A12") (pinfunction "31/A12_31/A12") (pintype "bidirectional"))
    )
    (net (code "127") (name "unconnected-(U$2-Pad32{slash}A13)") (class "Default")
      (node (ref "U$2") (pin "32/A13") (pinfunction "32/A13_32/A13") (pintype "bidirectional"))
    )
    (net (code "128") (name "unconnected-(U$2-PadA10)") (class "Default")
      (node (ref "U$2") (pin "A10") (pinfunction "A10_A10") (pintype "bidirectional"))
    )
    (net (code "129") (name "unconnected-(U$2-PadA11)") (class "Default")
      (node (ref "U$2") (pin "A11") (pinfunction "A11_A11") (pintype "bidirectional"))
    )
    (net (code "130") (name "unconnected-(U$2-PadA22{slash}DAC1)") (class "Default")
      (node (ref "U$2") (pin "A22/DAC1") (pinfunction "A22/DAC1_A22/DAC1") (pintype "bidirectional"))
    )
    (net (code "131") (name "unconnected-(U$2-PadPROG)") (class "Default")
      (node (ref "U$2") (pin "PROG") (pinfunction "PROG_PROG") (pintype "bidirectional"))
    )
    (net (code "132") (name "unconnected-(U$2-PadRESET)") (class "Default")
      (node (ref "U$2") (pin "RESET") (pinfunction "RESET_RESET") (pintype "bidirectional"))
    )
    (net (code "133") (name "unconnected-(U$2-PadU5V)") (class "Default")
      (node (ref "U$2") (pin "U5V") (pinfunction "U5V_U5V") (pintype "bidirectional"))
    )
    (net (code "134") (name "unconnected-(U$2-PadUD+)") (class "Default")
      (node (ref "U$2") (pin "UD+") (pinfunction "UD+_UD+") (pintype "bidirectional"))
    )
    (net (code "135") (name "unconnected-(U$2-PadUD-)") (class "Default")
      (node (ref "U$2") (pin "UD-") (pinfunction "UD-_UD-") (pintype "bidirectional"))
    )
    (net (code "136") (name "unconnected-(U$2-PadVBAT)") (class "Default")
      (node (ref "U$2") (pin "VBAT") (pinfunction "VBAT_VBAT") (pintype "bidirectional"))
    )
    (net (code "137") (name "unconnected-(U$2-PadVUSB)") (class "Default")
      (node (ref "U$2") (pin "VUSB") (pinfunction "VUSB_VUSB") (pintype "bidirectional"))
    )
  )
)
